# Power_Supply.net
KiCad netlist of a schematic drawn in Altium Designer
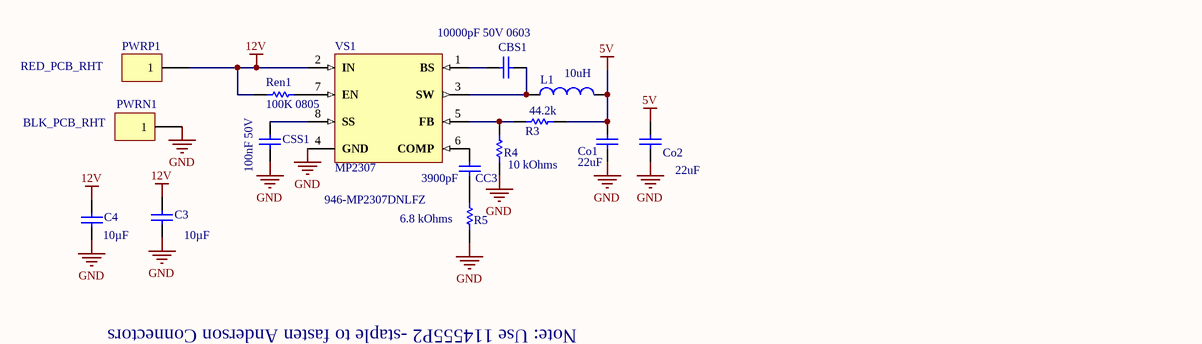
[diagram p0: Power Supply.SchDoc]

(export (version "E")
  (design (tool "Eeschema 10.0.6"))
  (components
    (comp (ref "C3")
      (value "10µF")
      (footprint "CAPC2013X135X45ML10T25")
      (fields
        (field (name "PART NUMBER") "GRM21BR61E106KA73L")
        (field (name "MANUFACTURER") "Murata")
        (field (name "TOLERANCE") "±10%")
      )
      (libsource (lib "Altium Content Vault") (part "CMP-2007-03541-1"))
    )
    (comp (ref "C4")
      (value "10µF")
      (footprint "CAPC2013X135X45ML10T25")
      (fields
        (field (name "PART NUMBER") "GRM21BR61E106KA73L")
        (field (name "MANUFACTURER") "Murata")
        (field (name "TOLERANCE") "±10%")
      )
      (libsource (lib "Altium Content Vault") (part "CMP-2007-03541-1"))
    )
    (comp (ref "CBS1")
      (value "10000pF 50V 0603")
      (footprint "0603C_L")
      (fields
        (field (name "MANUFACTURER") "Yageo")
        (field (name "MANUFACTURER PART NUMBER") "CC0603KRX7R9BB103")
        (field (name "TOLERANCE") "±10%")
      )
      (libsource (lib "ICEdigikey") (part "Cap10000pF_50V_0603"))
    )
    (comp (ref "CC3")
      (value "3900pF")
      (footprint "0603C_L")
      (fields
        (field (name "MANUFACTURER") "Murata")
        (field (name "MANUFACTURER PART NUMBER") "GRM188R71E392KA01D")
        (field (name "VOLTAGE") "25VDC")
      )
      (libsource (lib "ICEdigikey") (part "Cap_0603_1"))
    )
    (comp (ref "Co1")
      (value "22uF")
      (footprint "0603C_L")
      (fields
        (field (name "MANUFACTURER") "Murata")
        (field (name "MANUFACTURER PART NUMBER") "GRM188R60J226MEA0D")
        (field (name "VOLTAGE") "6.3VDC")
      )
      (libsource (lib "ICEdigikey") (part "Cap_0603_1"))
    )
    (comp (ref "Co2")
      (value "22uF")
      (footprint "0603C_L")
      (fields
        (field (name "MANUFACTURER") "Murata")
        (field (name "MANUFACTURER PART NUMBER") "GRM188R60J226MEA0D")
        (field (name "VOLTAGE") "6.3VDC")
      )
      (libsource (lib "ICEdigikey") (part "Cap_0603_1"))
    )
    (comp (ref "CSS1")
      (value "100nF 50V")
      (footprint "0603C_L")
      (fields
        (field (name "MANUFACTURER") "Yageo")
        (field (name "MANUFACTURER PART NUMBER") "CC0603ZRY5V9BB104")
        (field (name "TOLERANCE") "-20%, +80%")
      )
      (libsource (lib "PoleV2PaintV5") (part "Cap101nF_50V_0603"))
    )
    (comp (ref "L1")
      (value "10uH")
      (footprint "IND_1")
      (description "Inductor")
      (fields
        (field (name "MANUFACTURER") "Abracon")
        (field (name "MANUFACTURER PART NUMBER") "ASPI-0630LR-100M-T15")
        (field (name "PUBLISHER") "Altium Limited")
      )
      (libsource (lib "ICEdigikey") (part "Inductor"))
    )
    (comp (ref "PWRN1")
      (value "BLK_PCB_RHT")
      (footprint "Anderson_BLK_RHT_BOT")
      (description "1 pin Anderson")
      (fields
        (field (name "MANUFACTURER") "Anderson Power Products (APP)")
        (field (name "MANUFACTURER PART NUMBER") "1377G1, 1377G2, 1327-BK,137G6-BK")
      )
      (libsource (lib "ICEdigikey") (part "Anderson-1Pin BLK_PCB_RHT"))
    )
    (comp (ref "PWRP1")
      (value "RED_PCB_RHT")
      (footprint "Anderson_Red_RHT_BOT")
      (description "1 pin Anderson")
      (fields
        (field (name "MANUFACTURER") "Anderson Power Products (APP)")
        (field (name "MANUFACTURER PART NUMBER") "1377G1, 1377G2, 1327-BK,137G6-BK")
      )
      (libsource (lib "ICEdigikey") (part "Anderson-1Pin RED_PCB_RHT"))
    )
    (comp (ref "R3")
      (value "44.2k")
      (footprint "0805_L")
      (fields
        (field (name "MANUFACTURER") "Yageo")
        (field (name "MANUFACTURER PART NUMBER") "RC0805FR-0744K2L")
        (field (name "RESISTANCE (OHMS)") "44.2k")
        (field (name "TOLERANCE") "±1%")
      )
      (libsource (lib "ICEdigikey") (part "Res_0805"))
    )
    (comp (ref "R4")
      (value "10 kOhms")
      (footprint "0805_L")
      (fields
        (field (name "MANUFACTURER") "Yageo")
        (field (name "MANUFACTURER PART NUMBER") "RC0805FR-0710KL")
        (field (name "TOLERANCE") "1 %")
      )
      (libsource (lib "ICEdigikey") (part "Res_0805"))
    )
    (comp (ref "R5")
      (value "6.8 kOhms")
      (footprint "0805_L")
      (fields
        (field (name "MANUFACTURER") "Yageo")
        (field (name "MANUFACTURER PART NUMBER") "RC0805JR-076K8L")
        (field (name "TOLERANCE") "5 %")
      )
      (libsource (lib "ICEdigikey") (part "Res_0805"))
    )
    (comp (ref "Ren1")
      (value "100K 0805")
      (footprint "0805_L")
      (fields
        (field (name "MANUFACTURER") "Panasonic / Panasonic ECG")
        (field (name "MANUFACTURER PART NUMBER") "ERJ-6GEYJ104V")
      )
      (libsource (lib "ICEdigikey") (part "Res100K_080"))
    )
    (comp (ref "VS1")
      (value "MP2307")
      (footprint "SOIC8N_EXP")
      (fields
        (field (name "MANUFACTURER") "Monolithic Power Systems (MPS)")
        (field (name "MANUFACTURER PART NUMBER") "MP2307DN-LF-Z")
        (field (name "SUPPLIER PART NUMBER 1") "946-MP2307DNLFZ")
      )
      (libsource (lib "ICEdigikey") (part "MP2307"))
    )
  )
  (nets
    (net (code "1") (name "5V") (class "Default")
      (node (ref "Co1") (pin "2") (pinfunction "2_2") (pintype "passive"))
      (node (ref "Co2") (pin "2") (pinfunction "2_2") (pintype "passive"))
      (node (ref "L1") (pin "2") (pinfunction "2_2") (pintype "passive"))
      (node (ref "R3") (pin "1") (pinfunction "1_1") (pintype "passive"))
    )
    (net (code "2") (name "12V") (class "Default")
      (node (ref "C3") (pin "2") (pinfunction "2_2") (pintype "passive"))
      (node (ref "C4") (pin "2") (pinfunction "2_2") (pintype "passive"))
      (node (ref "PWRP1") (pin "1") (pinfunction "1_1") (pintype "passive"))
      (node (ref "Ren1") (pin "1") (pinfunction "1_1") (pintype "passive"))
      (node (ref "VS1") (pin "2") (pinfunction "IN_2") (pintype "input"))
    )
    (net (code "3") (name "GND") (class "Default")
      (node (ref "C3") (pin "1") (pinfunction "1_1") (pintype "passive"))
      (node (ref "C4") (pin "1") (pinfunction "1_1") (pintype "passive"))
      (node (ref "CSS1") (pin "1") (pinfunction "1_1") (pintype "passive"))
      (node (ref "Co1") (pin "1") (pinfunction "1_1") (pintype "passive"))
      (node (ref "Co2") (pin "1") (pinfunction "1_1") (pintype "passive"))
      (node (ref "PWRN1") (pin "1") (pinfunction "1_1") (pintype "passive"))
      (node (ref "R4") (pin "2") (pinfunction "2_2") (pintype "passive"))
      (node (ref "R5") (pin "1") (pinfunction "1_1") (pintype "passive"))
      (node (ref "VS1") (pin "4") (pinfunction "GND_4") (pintype "power_in"))
    )
    (net (code "4") (name "Net-(CC3-Pad1)") (class "Default")
      (node (ref "CC3") (pin "1") (pinfunction "1_1") (pintype "passive"))
      (node (ref "R5") (pin "2") (pinfunction "2_2") (pintype "passive"))
    )
    (net (code "5") (name "Net-(VS1-BS)") (class "Default")
      (node (ref "CBS1") (pin "2") (pinfunction "2_2") (pintype "passive"))
      (node (ref "VS1") (pin "1") (pinfunction "BS_1") (pintype "input"))
    )
    (net (code "6") (name "Net-(VS1-COMP)") (class "Default")
      (node (ref "CC3") (pin "2") (pinfunction "2_2") (pintype "passive"))
      (node (ref "VS1") (pin "6") (pinfunction "COMP_6") (pintype "input"))
    )
    (net (code "7") (name "Net-(VS1-EN)") (class "Default")
      (node (ref "Ren1") (pin "2") (pinfunction "2_2") (pintype "passive"))
      (node (ref "VS1") (pin "7") (pinfunction "EN_7") (pintype "input"))
    )
    (net (code "8") (name "Net-(VS1-FB)") (class "Default")
      (node (ref "R3") (pin "2") (pinfunction "2_2") (pintype "passive"))
      (node (ref "R4") (pin "1") (pinfunction "1_1") (pintype "passive"))
      (node (ref "VS1") (pin "5") (pinfunction "FB_5") (pintype "input"))
    )
    (net (code "9") (name "Net-(VS1-SS)") (class "Default")
      (node (ref "CSS1") (pin "2") (pinfunction "2_2") (pintype "passive"))
      (node (ref "VS1") (pin "8") (pinfunction "SS_8") (pintype "input"))
    )
    (net (code "10") (name "Net-(VS1-SW)") (class "Default")
      (node (ref "CBS1") (pin "1") (pinfunction "1_1") (pintype "passive"))
      (node (ref "L1") (pin "1") (pinfunction "1_1") (pintype "passive"))
      (node (ref "VS1") (pin "3") (pinfunction "SW_3") (pintype "output"))
    )
  )
)
